# OLED_Sheild.net
KiCad netlist of a schematic drawn in EAGLE
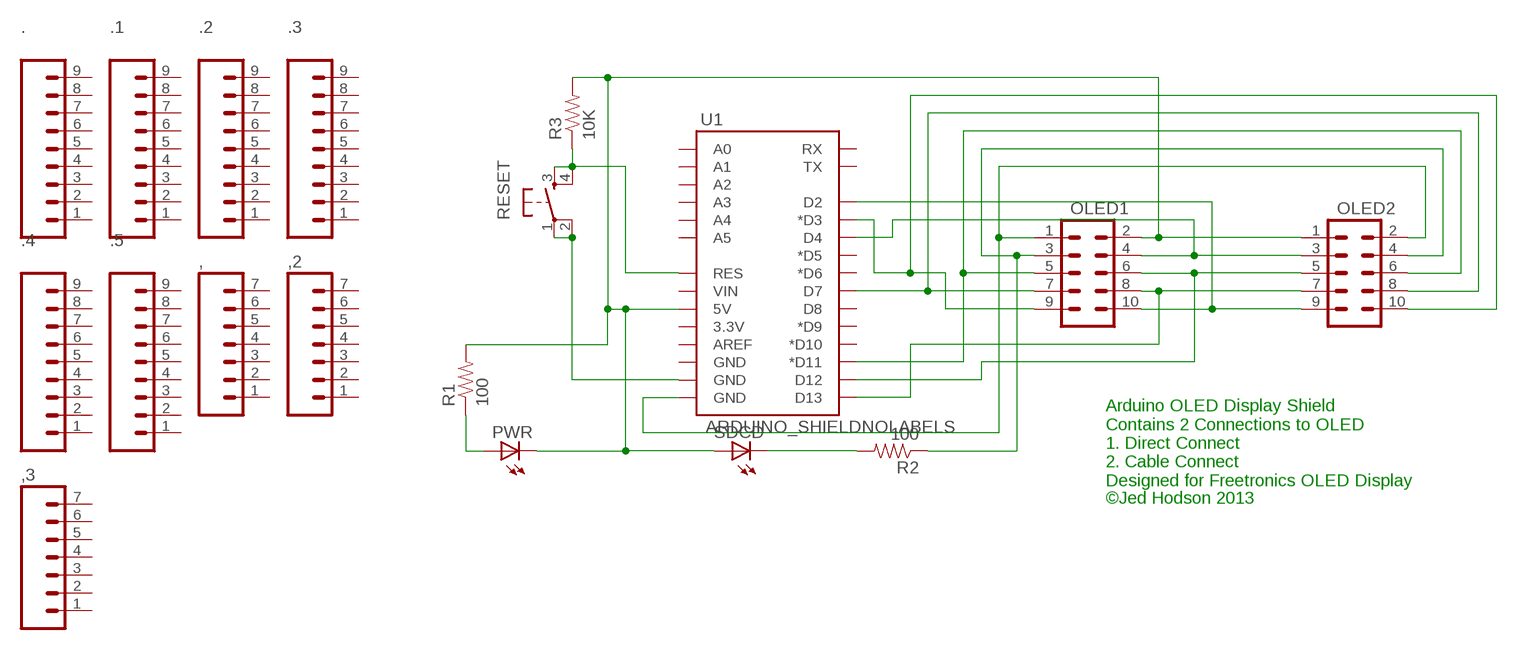
[diagram p0: schematic, sheet 1]

(export (version "E")
  (design (tool "Eeschema 10.0.6"))
  (components
    (comp (ref ",")
      (value "M07")
      (footprint "eagle-import:1X07")
      (libsource (lib "eagle-import") (part "M07"))
    )
    (comp (ref ",2")
      (value "M07")
      (footprint "eagle-import:1X07")
      (libsource (lib "eagle-import") (part "M07"))
    )
    (comp (ref ",3")
      (value "M07")
      (footprint "eagle-import:1X07")
      (libsource (lib "eagle-import") (part "M07"))
    )
    (comp (ref ".")
      (value "M09")
      (footprint "eagle-import:1X09")
      (libsource (lib "eagle-import") (part "M09"))
    )
    (comp (ref ".1")
      (value "M09")
      (footprint "eagle-import:1X09")
      (libsource (lib "eagle-import") (part "M09"))
    )
    (comp (ref ".2")
      (value "M09")
      (footprint "eagle-import:1X09")
      (libsource (lib "eagle-import") (part "M09"))
    )
    (comp (ref ".3")
      (value "M09")
      (footprint "eagle-import:1X09")
      (libsource (lib "eagle-import") (part "M09"))
    )
    (comp (ref ".4")
      (value "M09")
      (footprint "eagle-import:1X09")
      (libsource (lib "eagle-import") (part "M09"))
    )
    (comp (ref ".5")
      (value "M09")
      (footprint "eagle-import:1X09")
      (libsource (lib "eagle-import") (part "M09"))
    )
    (comp (ref "OLED1")
      (value "M05X2PTH")
      (footprint "eagle-import:AVR_ICSP")
      (libsource (lib "eagle-import") (part "M05X2PTH"))
    )
    (comp (ref "OLED2")
      (value "M05X2PTH")
      (footprint "eagle-import:AVR_ICSP")
      (libsource (lib "eagle-import") (part "M05X2PTH"))
    )
    (comp (ref "PWR")
      (value "LED5MM")
      (footprint "eagle-import:LED5MM")
      (libsource (lib "eagle-import") (part "LED5MM"))
    )
    (comp (ref "R1")
      (value "100")
      (footprint "eagle-import:AXIAL-0.4")
      (libsource (lib "eagle-import") (part "RESISTORPTH-1/4W"))
    )
    (comp (ref "R2")
      (value "100")
      (footprint "eagle-import:AXIAL-0.4")
      (libsource (lib "eagle-import") (part "RESISTORPTH-1/4W"))
    )
    (comp (ref "R3")
      (value "10K")
      (footprint "eagle-import:AXIAL-0.4")
      (libsource (lib "eagle-import") (part "RESISTORPTH-1/4W"))
    )
    (comp (ref "RESET")
      (value "TAC_SWITCHPTH")
      (footprint "eagle-import:TACTILE-PTH")
      (libsource (lib "eagle-import") (part "TAC_SWITCHPTH"))
    )
    (comp (ref "SDCD")
      (value "LED5MM")
      (footprint "eagle-import:LED5MM")
      (libsource (lib "eagle-import") (part "LED5MM"))
    )
    (comp (ref "U1")
      (value "ARDUINO_SHIELDNOLABELS")
      (footprint "eagle-import:DUEMILANOVE_SHIELD_NOLABELS")
      (libsource (lib "eagle-import") (part "ARDUINO_SHIELDNOLABELS"))
    )
  )
  (nets
    (net (code "1") (name "Net-(OLED1-Pad1)") (class "Default")
      (node (ref "OLED1") (pin "1") (pinfunction "1_1") (pintype "passive"))
      (node (ref "OLED2") (pin "2") (pinfunction "2_2") (pintype "passive"))
      (node (ref "U1") (pin "GND@0") (pinfunction "GND_GND@0") (pintype "bidirectional"))
    )
    (net (code "2") (name "Net-(OLED1-Pad4)") (class "Default")
      (node (ref "OLED1") (pin "4") (pinfunction "4_4") (pintype "passive"))
      (node (ref "OLED2") (pin "3") (pinfunction "3_3") (pintype "passive"))
      (node (ref "U1") (pin "D4") (pinfunction "D4_D4") (pintype "bidirectional"))
    )
    (net (code "3") (name "Net-(OLED1-Pad6)") (class "Default")
      (node (ref "OLED1") (pin "6") (pinfunction "6_6") (pintype "passive"))
      (node (ref "OLED2") (pin "5") (pinfunction "5_5") (pintype "passive"))
      (node (ref "U1") (pin "D12") (pinfunction "D12_D12") (pintype "bidirectional"))
    )
    (net (code "4") (name "Net-(OLED1-Pad7)") (class "Default")
      (node (ref "OLED1") (pin "7") (pinfunction "7_7") (pintype "passive"))
      (node (ref "OLED2") (pin "8") (pinfunction "8_8") (pintype "passive"))
      (node (ref "U1") (pin "D7") (pinfunction "D7_D7") (pintype "bidirectional"))
    )
    (net (code "5") (name "Net-(OLED1-Pad8)") (class "Default")
      (node (ref "OLED1") (pin "8") (pinfunction "8_8") (pintype "passive"))
      (node (ref "OLED2") (pin "7") (pinfunction "7_7") (pintype "passive"))
      (node (ref "U1") (pin "D13") (pinfunction "D13_D13") (pintype "bidirectional"))
    )
    (net (code "6") (name "Net-(OLED1-Pad10)") (class "Default")
      (node (ref "OLED1") (pin "10") (pinfunction "10_10") (pintype "passive"))
      (node (ref "OLED2") (pin "9") (pinfunction "9_9") (pintype "passive"))
      (node (ref "U1") (pin "D2") (pinfunction "D2_D2") (pintype "bidirectional"))
    )
    (net (code "7") (name "Net-(PWR-C)") (class "Default")
      (node (ref "OLED1") (pin "2") (pinfunction "2_2") (pintype "passive"))
      (node (ref "OLED2") (pin "1") (pinfunction "1_1") (pintype "passive"))
      (node (ref "PWR") (pin "K") (pinfunction "C_K") (pintype "passive"))
      (node (ref "R1") (pin "P$2") (pinfunction "2_P$2") (pintype "passive"))
      (node (ref "R3") (pin "P$2") (pinfunction "2_P$2") (pintype "passive"))
      (node (ref "SDCD") (pin "A") (pinfunction "A_A") (pintype "passive"))
      (node (ref "U1") (pin "5V") (pinfunction "5V_5V") (pintype "bidirectional"))
    )
    (net (code "8") (name "Net-(R1-1)") (class "Default")
      (node (ref "PWR") (pin "A") (pinfunction "A_A") (pintype "passive"))
      (node (ref "R1") (pin "P$1") (pinfunction "1_P$1") (pintype "passive"))
    )
    (net (code "9") (name "Net-(R2-1)") (class "Default")
      (node (ref "OLED1") (pin "3") (pinfunction "3_3") (pintype "passive"))
      (node (ref "OLED2") (pin "4") (pinfunction "4_4") (pintype "passive"))
      (node (ref "R2") (pin "P$1") (pinfunction "1_P$1") (pintype "passive"))
    )
    (net (code "10") (name "Net-(R2-2)") (class "Default")
      (node (ref "R2") (pin "P$2") (pinfunction "2_P$2") (pintype "passive"))
      (node (ref "SDCD") (pin "K") (pinfunction "C_K") (pintype "passive"))
    )
    (net (code "11") (name "Net-(R3-1)") (class "Default")
      (node (ref "R3") (pin "P$1") (pinfunction "1_P$1") (pintype "passive"))
      (node (ref "RESET") (pin "3") (pinfunction "3_3") (pintype "passive"))
      (node (ref "RESET") (pin "4") (pinfunction "4_4") (pintype "passive"))
      (node (ref "U1") (pin "RES") (pinfunction "RES_RES") (pintype "bidirectional"))
    )
    (net (code "12") (name "Net-(RESET-Pad1)") (class "Default")
      (node (ref "RESET") (pin "1") (pinfunction "1_1") (pintype "passive"))
      (node (ref "RESET") (pin "2") (pinfunction "2_2") (pintype "passive"))
      (node (ref "U1") (pin "GND@1") (pinfunction "GND_GND@1") (pintype "bidirectional"))
    )
    (net (code "13") (name "Net-(U1-*D3)") (class "Default")
      (node (ref "OLED1") (pin "9") (pinfunction "9_9") (pintype "passive"))
      (node (ref "OLED2") (pin "10") (pinfunction "10_10") (pintype "passive"))
      (node (ref "U1") (pin "D3") (pinfunction "*D3_D3") (pintype "bidirectional"))
    )
    (net (code "14") (name "Net-(U1-*D11)") (class "Default")
      (node (ref "OLED1") (pin "5") (pinfunction "5_5") (pintype "passive"))
      (node (ref "OLED2") (pin "6") (pinfunction "6_6") (pintype "passive"))
      (node (ref "U1") (pin "D11") (pinfunction "*D11_D11") (pintype "bidirectional"))
    )
    (net (code "15") (name "unconnected-(,-Pad1)") (class "Default")
      (node (ref ",") (pin "1") (pinfunction "1_1") (pintype "passive"))
    )
    (net (code "16") (name "unconnected-(,-Pad2)") (class "Default")
      (node (ref ",") (pin "2") (pinfunction "2_2") (pintype "passive"))
    )
    (net (code "17") (name "unconnected-(,-Pad3)") (class "Default")
      (node (ref ",") (pin "3") (pinfunction "3_3") (pintype "passive"))
    )
    (net (code "18") (name "unconnected-(,-Pad4)") (class "Default")
      (node (ref ",") (pin "4") (pinfunction "4_4") (pintype "passive"))
    )
    (net (code "19") (name "unconnected-(,-Pad5)") (class "Default")
      (node (ref ",") (pin "5") (pinfunction "5_5") (pintype "passive"))
    )
    (net (code "20") (name "unconnected-(,-Pad6)") (class "Default")
      (node (ref ",") (pin "6") (pinfunction "6_6") (pintype "passive"))
    )
    (net (code "21") (name "unconnected-(,-Pad7)") (class "Default")
      (node (ref ",") (pin "7") (pinfunction "7_7") (pintype "passive"))
    )
    (net (code "22") (name "unconnected-(,2-Pad1)") (class "Default")
      (node (ref ",2") (pin "1") (pinfunction "1_1") (pintype "passive"))
    )
    (net (code "23") (name "unconnected-(,2-Pad2)") (class "Default")
      (node (ref ",2") (pin "2") (pinfunction "2_2") (pintype "passive"))
    )
    (net (code "24") (name "unconnected-(,2-Pad3)") (class "Default")
      (node (ref ",2") (pin "3") (pinfunction "3_3") (pintype "passive"))
    )
    (net (code "25") (name "unconnected-(,2-Pad4)") (class "Default")
      (node (ref ",2") (pin "4") (pinfunction "4_4") (pintype "passive"))
    )
    (net (code "26") (name "unconnected-(,2-Pad5)") (class "Default")
      (node (ref ",2") (pin "5") (pinfunction "5_5") (pintype "passive"))
    )
    (net (code "27") (name "unconnected-(,2-Pad6)") (class "Default")
      (node (ref ",2") (pin "6") (pinfunction "6_6") (pintype "passive"))
    )
    (net (code "28") (name "unconnected-(,2-Pad7)") (class "Default")
      (node (ref ",2") (pin "7") (pinfunction "7_7") (pintype "passive"))
    )
    (net (code "29") (name "unconnected-(,3-Pad1)") (class "Default")
      (node (ref ",3") (pin "1") (pinfunction "1_1") (pintype "passive"))
    )
    (net (code "30") (name "unconnected-(,3-Pad2)") (class "Default")
      (node (ref ",3") (pin "2") (pinfunction "2_2") (pintype "passive"))
    )
    (net (code "31") (name "unconnected-(,3-Pad3)") (class "Default")
      (node (ref ",3") (pin "3") (pinfunction "3_3") (pintype "passive"))
    )
    (net (code "32") (name "unconnected-(,3-Pad4)") (class "Default")
      (node (ref ",3") (pin "4") (pinfunction "4_4") (pintype "passive"))
    )
    (net (code "33") (name "unconnected-(,3-Pad5)") (class "Default")
      (node (ref ",3") (pin "5") (pinfunction "5_5") (pintype "passive"))
    )
    (net (code "34") (name "unconnected-(,3-Pad6)") (class "Default")
      (node (ref ",3") (pin "6") (pinfunction "6_6") (pintype "passive"))
    )
    (net (code "35") (name "unconnected-(,3-Pad7)") (class "Default")
      (node (ref ",3") (pin "7") (pinfunction "7_7") (pintype "passive"))
    )
    (net (code "36") (name "unconnected-(.-Pad1)") (class "Default")
      (node (ref ".") (pin "1") (pinfunction "1_1") (pintype "passive"))
    )
    (net (code "37") (name "unconnected-(.-Pad2)") (class "Default")
      (node (ref ".") (pin "2") (pinfunction "2_2") (pintype "passive"))
    )
    (net (code "38") (name "unconnected-(.-Pad3)") (class "Default")
      (node (ref ".") (pin "3") (pinfunction "3_3") (pintype "passive"))
    )
    (net (code "39") (name "unconnected-(.-Pad4)") (class "Default")
      (node (ref ".") (pin "4") (pinfunction "4_4") (pintype "passive"))
    )
    (net (code "40") (name "unconnected-(.-Pad5)") (class "Default")
      (node (ref ".") (pin "5") (pinfunction "5_5") (pintype "passive"))
    )
    (net (code "41") (name "unconnected-(.-Pad6)") (class "Default")
      (node (ref ".") (pin "6") (pinfunction "6_6") (pintype "passive"))
    )
    (net (code "42") (name "unconnected-(.-Pad7)") (class "Default")
      (node (ref ".") (pin "7") (pinfunction "7_7") (pintype "passive"))
    )
    (net (code "43") (name "unconnected-(.-Pad8)") (class "Default")
      (node (ref ".") (pin "8") (pinfunction "8_8") (pintype "passive"))
    )
    (net (code "44") (name "unconnected-(.-Pad9)") (class "Default")
      (node (ref ".") (pin "9") (pinfunction "9_9") (pintype "passive"))
    )
    (net (code "45") (name "unconnected-(.1-Pad1)") (class "Default")
      (node (ref ".1") (pin "1") (pinfunction "1_1") (pintype "passive"))
    )
    (net (code "46") (name "unconnected-(.1-Pad2)") (class "Default")
      (node (ref ".1") (pin "2") (pinfunction "2_2") (pintype "passive"))
    )
    (net (code "47") (name "unconnected-(.1-Pad3)") (class "Default")
      (node (ref ".1") (pin "3") (pinfunction "3_3") (pintype "passive"))
    )
    (net (code "48") (name "unconnected-(.1-Pad4)") (class "Default")
      (node (ref ".1") (pin "4") (pinfunction "4_4") (pintype "passive"))
    )
    (net (code "49") (name "unconnected-(.1-Pad5)") (class "Default")
      (node (ref ".1") (pin "5") (pinfunction "5_5") (pintype "passive"))
    )
    (net (code "50") (name "unconnected-(.1-Pad6)") (class "Default")
      (node (ref ".1") (pin "6") (pinfunction "6_6") (pintype "passive"))
    )
    (net (code "51") (name "unconnected-(.1-Pad7)") (class "Default")
      (node (ref ".1") (pin "7") (pinfunction "7_7") (pintype "passive"))
    )
    (net (code "52") (name "unconnected-(.1-Pad8)") (class "Default")
      (node (ref ".1") (pin "8") (pinfunction "8_8") (pintype "passive"))
    )
    (net (code "53") (name "unconnected-(.1-Pad9)") (class "Default")
      (node (ref ".1") (pin "9") (pinfunction "9_9") (pintype "passive"))
    )
    (net (code "54") (name "unconnected-(.2-Pad1)") (class "Default")
      (node (ref ".2") (pin "1") (pinfunction "1_1") (pintype "passive"))
    )
    (net (code "55") (name "unconnected-(.2-Pad2)") (class "Default")
      (node (ref ".2") (pin "2") (pinfunction "2_2") (pintype "passive"))
    )
    (net (code "56") (name "unconnected-(.2-Pad3)") (class "Default")
      (node (ref ".2") (pin "3") (pinfunction "3_3") (pintype "passive"))
    )
    (net (code "57") (name "unconnected-(.2-Pad4)") (class "Default")
      (node (ref ".2") (pin "4") (pinfunction "4_4") (pintype "passive"))
    )
    (net (code "58") (name "unconnected-(.2-Pad5)") (class "Default")
      (node (ref ".2") (pin "5") (pinfunction "5_5") (pintype "passive"))
    )
    (net (code "59") (name "unconnected-(.2-Pad6)") (class "Default")
      (node (ref ".2") (pin "6") (pinfunction "6_6") (pintype "passive"))
    )
    (net (code "60") (name "unconnected-(.2-Pad7)") (class "Default")
      (node (ref ".2") (pin "7") (pinfunction "7_7") (pintype "passive"))
    )
    (net (code "61") (name "unconnected-(.2-Pad8)") (class "Default")
      (node (ref ".2") (pin "8") (pinfunction "8_8") (pintype "passive"))
    )
    (net (code "62") (name "unconnected-(.2-Pad9)") (class "Default")
      (node (ref ".2") (pin "9") (pinfunction "9_9") (pintype "passive"))
    )
    (net (code "63") (name "unconnected-(.3-Pad1)") (class "Default")
      (node (ref ".3") (pin "1") (pinfunction "1_1") (pintype "passive"))
    )
    (net (code "64") (name "unconnected-(.3-Pad2)") (class "Default")
      (node (ref ".3") (pin "2") (pinfunction "2_2") (pintype "passive"))
    )
    (net (code "65") (name "unconnected-(.3-Pad3)") (class "Default")
      (node (ref ".3") (pin "3") (pinfunction "3_3") (pintype "passive"))
    )
    (net (code "66") (name "unconnected-(.3-Pad4)") (class "Default")
      (node (ref ".3") (pin "4") (pinfunction "4_4") (pintype "passive"))
    )
    (net (code "67") (name "unconnected-(.3-Pad5)") (class "Default")
      (node (ref ".3") (pin "5") (pinfunction "5_5") (pintype "passive"))
    )
    (net (code "68") (name "unconnected-(.3-Pad6)") (class "Default")
      (node (ref ".3") (pin "6") (pinfunction "6_6") (pintype "passive"))
    )
    (net (code "69") (name "unconnected-(.3-Pad7)") (class "Default")
      (node (ref ".3") (pin "7") (pinfunction "7_7") (pintype "passive"))
    )
    (net (code "70") (name "unconnected-(.3-Pad8)") (class "Default")
      (node (ref ".3") (pin "8") (pinfunction "8_8") (pintype "passive"))
    )
    (net (code "71") (name "unconnected-(.3-Pad9)") (class "Default")
      (node (ref ".3") (pin "9") (pinfunction "9_9") (pintype "passive"))
    )
    (net (code "72") (name "unconnected-(.4-Pad1)") (class "Default")
      (node (ref ".4") (pin "1") (pinfunction "1_1") (pintype "passive"))
    )
    (net (code "73") (name "unconnected-(.4-Pad2)") (class "Default")
      (node (ref ".4") (pin "2") (pinfunction "2_2") (pintype "passive"))
    )
    (net (code "74") (name "unconnected-(.4-Pad3)") (class "Default")
      (node (ref ".4") (pin "3") (pinfunction "3_3") (pintype "passive"))
    )
    (net (code "75") (name "unconnected-(.4-Pad4)") (class "Default")
      (node (ref ".4") (pin "4") (pinfunction "4_4") (pintype "passive"))
    )
    (net (code "76") (name "unconnected-(.4-Pad5)") (class "Default")
      (node (ref ".4") (pin "5") (pinfunction "5_5") (pintype "passive"))
    )
    (net (code "77") (name "unconnected-(.4-Pad6)") (class "Default")
      (node (ref ".4") (pin "6") (pinfunction "6_6") (pintype "passive"))
    )
    (net (code "78") (name "unconnected-(.4-Pad7)") (class "Default")
      (node (ref ".4") (pin "7") (pinfunction "7_7") (pintype "passive"))
    )
    (net (code "79") (name "unconnected-(.4-Pad8)") (class "Default")
      (node (ref ".4") (pin "8") (pinfunction "8_8") (pintype "passive"))
    )
    (net (code "80") (name "unconnected-(.4-Pad9)") (class "Default")
      (node (ref ".4") (pin "9") (pinfunction "9_9") (pintype "passive"))
    )
    (net (code "81") (name "unconnected-(.5-Pad1)") (class "Default")
      (node (ref ".5") (pin "1") (pinfunction "1_1") (pintype "passive"))
    )
    (net (code "82") (name "unconnected-(.5-Pad2)") (class "Default")
      (node (ref ".5") (pin "2") (pinfunction "2_2") (pintype "passive"))
    )
    (net (code "83") (name "unconnected-(.5-Pad3)") (class "Default")
      (node (ref ".5") (pin "3") (pinfunction "3_3") (pintype "passive"))
    )
    (net (code "84") (name "unconnected-(.5-Pad4)") (class "Default")
      (node (ref ".5") (pin "4") (pinfunction "4_4") (pintype "passive"))
    )
    (net (code "85") (name "unconnected-(.5-Pad5)") (class "Default")
      (node (ref ".5") (pin "5") (pinfunction "5_5") (pintype "passive"))
    )
    (net (code "86") (name "unconnected-(.5-Pad6)") (class "Default")
      (node (ref ".5") (pin "6") (pinfunction "6_6") (pintype "passive"))
    )
    (net (code "87") (name "unconnected-(.5-Pad7)") (class "Default")
      (node (ref ".5") (pin "7") (pinfunction "7_7") (pintype "passive"))
    )
    (net (code "88") (name "unconnected-(.5-Pad8)") (class "Default")
      (node (ref ".5") (pin "8") (pinfunction "8_8") (pintype "passive"))
    )
    (net (code "89") (name "unconnected-(.5-Pad9)") (class "Default")
      (node (ref ".5") (pin "9") (pinfunction "9_9") (pintype "passive"))
    )
    (net (code "90") (name "unconnected-(U1-*D5-PadD5)") (class "Default")
      (node (ref "U1") (pin "D5") (pinfunction "*D5_D5") (pintype "bidirectional"))
    )
    (net (code "91") (name "unconnected-(U1-*D6-PadD6)") (class "Default")
      (node (ref "U1") (pin "D6") (pinfunction "*D6_D6") (pintype "bidirectional"))
    )
    (net (code "92") (name "unconnected-(U1-*D9-PadD9)") (class "Default")
      (node (ref "U1") (pin "D9") (pinfunction "*D9_D9") (pintype "bidirectional"))
    )
    (net (code "93") (name "unconnected-(U1-*D10-PadD10)") (class "Default")
      (node (ref "U1") (pin "D10") (pinfunction "*D10_D10") (pintype "bidirectional"))
    )
    (net (code "94") (name "unconnected-(U1-GND-PadGND@2)") (class "Default")
      (node (ref "U1") (pin "GND@2") (pinfunction "GND_GND@2") (pintype "bidirectional"))
    )
    (net (code "95") (name "unconnected-(U1-Pad3.3V)") (class "Default")
      (node (ref "U1") (pin "3.3V") (pinfunction "3.3V_3.3V") (pintype "bidirectional"))
    )
    (net (code "96") (name "unconnected-(U1-PadA0)") (class "Default")
      (node (ref "U1") (pin "A0") (pinfunction "A0_A0") (pintype "bidirectional"))
    )
    (net (code "97") (name "unconnected-(U1-PadA1)") (class "Default")
      (node (ref "U1") (pin "A1") (pinfunction "A1_A1") (pintype "bidirectional"))
    )
    (net (code "98") (name "unconnected-(U1-PadA2)") (class "Default")
      (node (ref "U1") (pin "A2") (pinfunction "A2_A2") (pintype "bidirectional"))
    )
    (net (code "99") (name "unconnected-(U1-PadA3)") (class "Default")
      (node (ref "U1") (pin "A3") (pinfunction "A3_A3") (pintype "bidirectional"))
    )
    (net (code "100") (name "unconnected-(U1-PadA4)") (class "Default")
      (node (ref "U1") (pin "A4") (pinfunction "A4_A4") (pintype "bidirectional"))
    )
    (net (code "101") (name "unconnected-(U1-PadA5)") (class "Default")
      (node (ref "U1") (pin "A5") (pinfunction "A5_A5") (pintype "bidirectional"))
    )
    (net (code "102") (name "unconnected-(U1-PadAREF)") (class "Default")
      (node (ref "U1") (pin "AREF") (pinfunction "AREF_AREF") (pintype "bidirectional"))
    )
    (net (code "103") (name "unconnected-(U1-PadD8)") (class "Default")
      (node (ref "U1") (pin "D8") (pinfunction "D8_D8") (pintype "bidirectional"))
    )
    (net (code "104") (name "unconnected-(U1-PadRX)") (class "Default")
      (node (ref "U1") (pin "RX") (pinfunction "RX_RX") (pintype "bidirectional"))
    )
    (net (code "105") (name "unconnected-(U1-PadTX)") (class "Default")
      (node (ref "U1") (pin "TX") (pinfunction "TX_TX") (pintype "bidirectional"))
    )
    (net (code "106") (name "unconnected-(U1-PadVIN)") (class "Default")
      (node (ref "U1") (pin "VIN") (pinfunction "VIN_VIN") (pintype "bidirectional"))
    )
  )
)
